# BV100011_ControlIsolator.net
KiCad netlist of a schematic drawn in Altium Designer
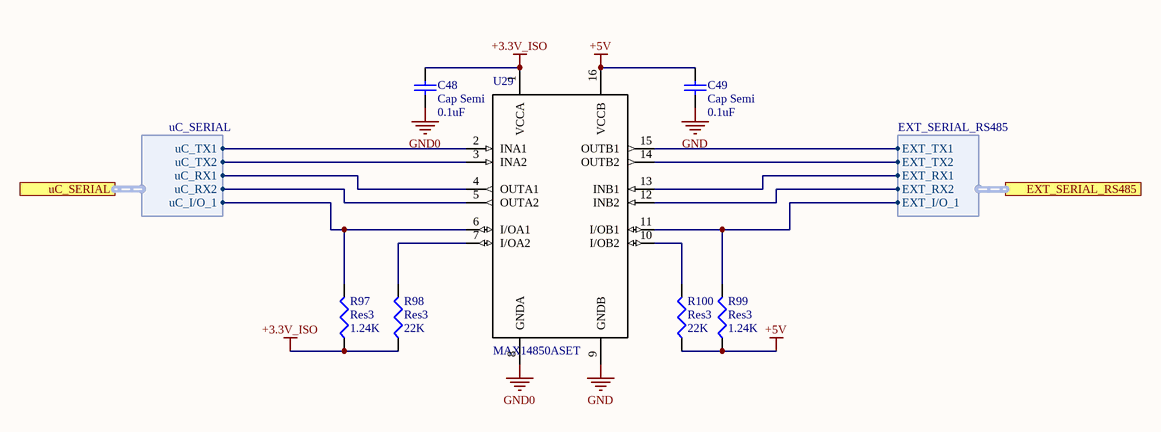
[diagram p0: BV100011_ControlIsolator.SchDoc]

(export (version "E")
  (design (tool "Eeschema 10.0.6"))
  (components
    (comp (ref "C48")
      (value "Cap Semi")
      (footprint "C1206")
      (description "Capacitor (Semiconductor SIM Model)")
      (fields (field (name "ALTIUM_VALUE") "0.1uF") (field (name "PUBLISHER") "Altium Limited"))
      (libsource (lib "Miscellaneous Devices") (part "Cap Semi"))
    )
    (comp (ref "C49")
      (value "Cap Semi")
      (footprint "C1206")
      (description "Capacitor (Semiconductor SIM Model)")
      (fields (field (name "ALTIUM_VALUE") "0.1uF") (field (name "PUBLISHER") "Altium Limited"))
      (libsource (lib "Miscellaneous Devices") (part "Cap Semi"))
    )
    (comp (ref "R97")
      (value "Res3")
      (footprint "J1-0603")
      (description "Resistor")
      (fields (field (name "ALTIUM_VALUE") "1.24K") (field (name "PUBLISHER") "Altium Limited"))
      (libsource (lib "Miscellaneous Devices") (part "Res3"))
    )
    (comp (ref "R98")
      (value "Res3")
      (footprint "J1-0603")
      (description "Resistor")
      (fields (field (name "ALTIUM_VALUE") "22K") (field (name "PUBLISHER") "Altium Limited"))
      (libsource (lib "Miscellaneous Devices") (part "Res3"))
    )
    (comp (ref "R99")
      (value "Res3")
      (footprint "J1-0603")
      (description "Resistor")
      (fields (field (name "ALTIUM_VALUE") "1.24K") (field (name "PUBLISHER") "Altium Limited"))
      (libsource (lib "Miscellaneous Devices") (part "Res3"))
    )
    (comp (ref "R100")
      (value "Res3")
      (footprint "J1-0603")
      (description "Resistor")
      (fields (field (name "ALTIUM_VALUE") "22K") (field (name "PUBLISHER") "Altium Limited"))
      (libsource (lib "Miscellaneous Devices") (part "Res3"))
    )
    (comp (ref "U29")
      (value "MAX14850ASET")
      (footprint "*SOIC127P600X175-16N")
      (description "Digital Isolator, 6-Ch, 30ns, Nsoic-16")
      (fields (field (name "MF") "Maxim Integrated") (field (name "MP") "MAX14850ASE+"))
      (libsource (lib "MAX14850ASET") (part "MAX14850ASET"))
    )
  )
  (nets
    (net (code "3") (name "+3.3V_ISO") (class "Default")
      (node (ref "C48") (pin "1") (pinfunction "1_1") (pintype "passive"))
      (node (ref "R97") (pin "1") (pinfunction "1_1") (pintype "passive"))
      (node (ref "R98") (pin "1") (pinfunction "1_1") (pintype "passive"))
      (node (ref "U29") (pin "1") (pinfunction "VCCA_1") (pintype "power_in"))
    )
    (net (code "4") (name "+5V") (class "Default")
      (node (ref "C49") (pin "1") (pinfunction "1_1") (pintype "passive"))
      (node (ref "R100") (pin "1") (pinfunction "1_1") (pintype "passive"))
      (node (ref "R99") (pin "1") (pinfunction "1_1") (pintype "passive"))
      (node (ref "U29") (pin "16") (pinfunction "VCCB_16") (pintype "power_in"))
    )
    (net (code "5") (name "/EXT_I{slash}O_1") (class "Default")
      (node (ref "R99") (pin "2") (pinfunction "2_2") (pintype "passive"))
      (node (ref "U29") (pin "11") (pinfunction "I/OB1_11") (pintype "bidirectional"))
    )
    (net (code "6") (name "/EXT_RX1") (class "Default")
      (node (ref "U29") (pin "13") (pinfunction "INB1_13") (pintype "input"))
    )
    (net (code "7") (name "/EXT_RX2") (class "Default")
      (node (ref "U29") (pin "12") (pinfunction "INB2_12") (pintype "input"))
    )
    (net (code "8") (name "/EXT_TX1") (class "Default")
      (node (ref "U29") (pin "15") (pinfunction "OUTB1_15") (pintype "output"))
    )
    (net (code "9") (name "/EXT_TX2") (class "Default")
      (node (ref "U29") (pin "14") (pinfunction "OUTB2_14") (pintype "output"))
    )
    (net (code "10") (name "/uC_I{slash}O_1") (class "Default")
      (node (ref "R97") (pin "2") (pinfunction "2_2") (pintype "passive"))
      (node (ref "U29") (pin "6") (pinfunction "I/OA1_6") (pintype "bidirectional"))
    )
    (net (code "11") (name "/uC_RX1") (class "Default")
      (node (ref "U29") (pin "4") (pinfunction "OUTA1_4") (pintype "output"))
    )
    (net (code "12") (name "/uC_RX2") (class "Default")
      (node (ref "U29") (pin "5") (pinfunction "OUTA2_5") (pintype "output"))
    )
    (net (code "13") (name "/uC_TX1") (class "Default")
      (node (ref "U29") (pin "2") (pinfunction "INA1_2") (pintype "input"))
    )
    (net (code "14") (name "/uC_TX2") (class "Default")
      (node (ref "U29") (pin "3") (pinfunction "INA2_3") (pintype "input"))
    )
    (net (code "17") (name "GND") (class "Default")
      (node (ref "C49") (pin "2") (pinfunction "2_2") (pintype "passive"))
      (node (ref "U29") (pin "9") (pinfunction "GNDB_9") (pintype "power_in"))
    )
    (net (code "18") (name "GND0") (class "Default")
      (node (ref "C48") (pin "2") (pinfunction "2_2") (pintype "passive"))
      (node (ref "U29") (pin "8") (pinfunction "GNDA_8") (pintype "power_in"))
    )
    (net (code "19") (name "Net-(U29-I{slash}OA2)") (class "Default")
      (node (ref "R98") (pin "2") (pinfunction "2_2") (pintype "passive"))
      (node (ref "U29") (pin "7") (pinfunction "I/OA2_7") (pintype "bidirectional"))
    )
    (net (code "20") (name "Net-(U29-I{slash}OB2)") (class "Default")
      (node (ref "R100") (pin "2") (pinfunction "2_2") (pintype "passive"))
      (node (ref "U29") (pin "10") (pinfunction "I/OB2_10") (pintype "bidirectional"))
    )
  )
)
